# Sheet_Robo_Hand_main.net
KiCad netlist of a schematic drawn in Altium Designer
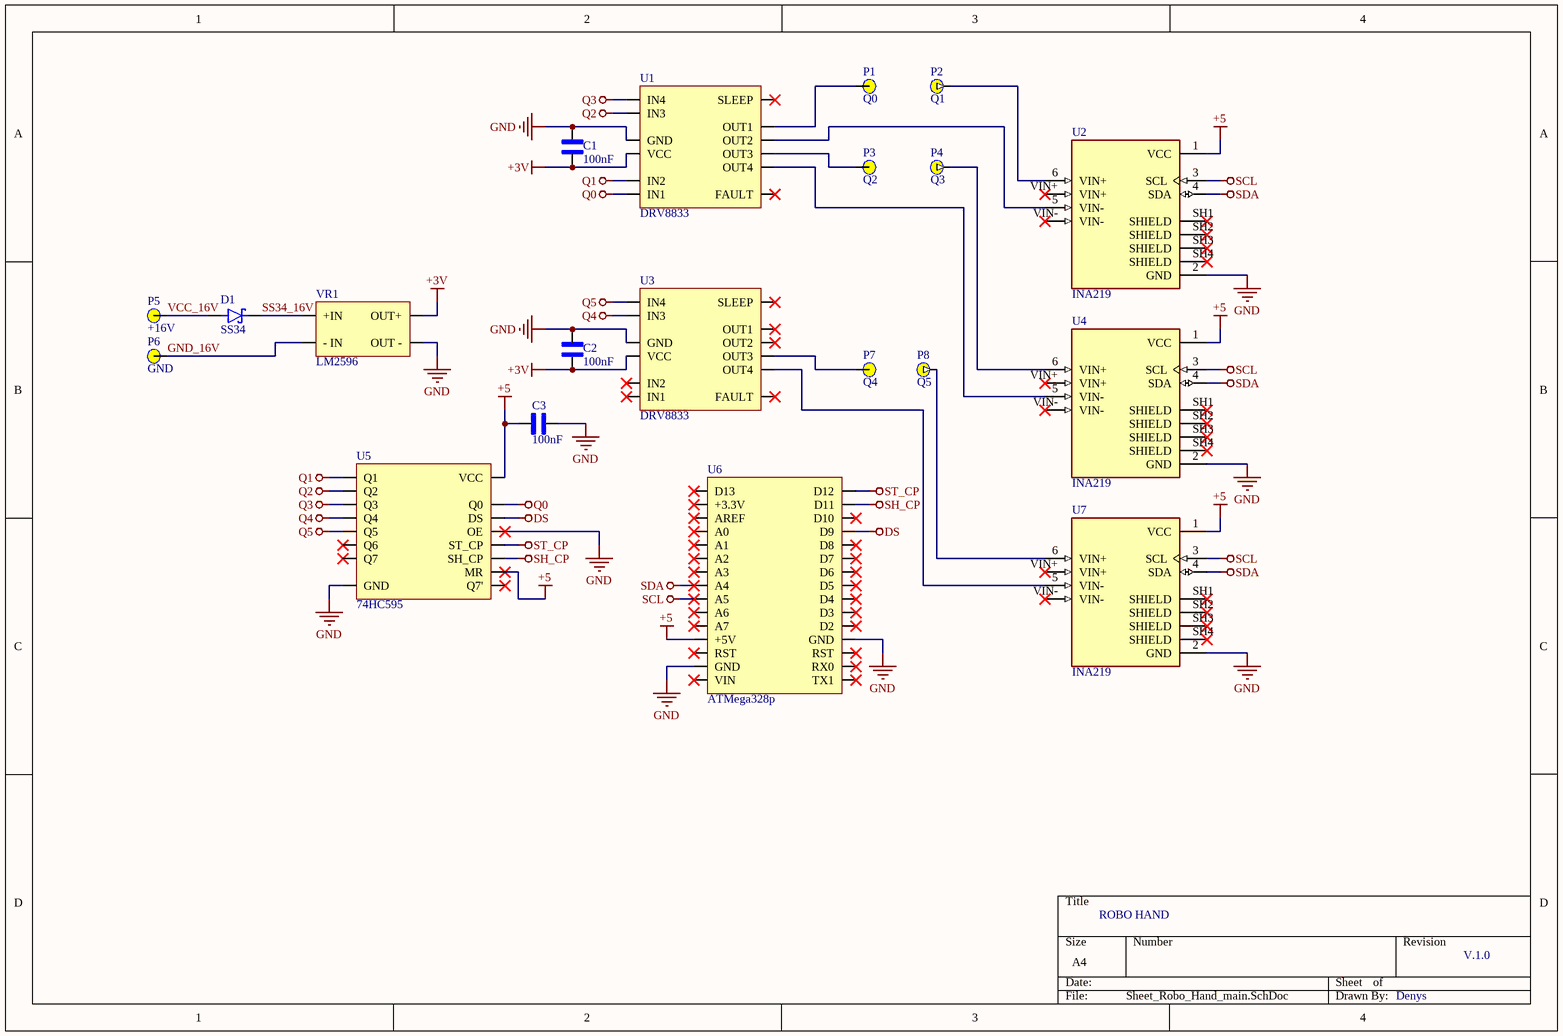
[diagram p0: Sheet_Robo_Hand_main.SchDoc]

(export (version "E")
  (design (tool "Eeschema 10.0.6"))
  (components
    (comp (ref "C1")
      (value "100nF")
      (footprint "CAPC3216X180N")
      (description "Ceramic capacitor SMD 1206 100 nF 50 V 10 % Samsung Electro-Mechanics CL31B104KBCNNNC 4000 pc(s)")
      (fields (field (name "MP") "CL31B104KBCNNNC") (field (name "MF") "Samsung Electro-Mechanics"))
      (libsource (lib "") (part "C_1206_100nF_1"))
    )
    (comp (ref "C2")
      (value "100nF")
      (footprint "CAPC3216X180N")
      (description "Ceramic capacitor SMD 1206 100 nF 50 V 10 % Samsung Electro-Mechanics CL31B104KBCNNNC 4000 pc(s)")
      (fields (field (name "MP") "CL31B104KBCNNNC") (field (name "MF") "Samsung Electro-Mechanics"))
      (libsource (lib "С_1206_100nF") (part "C_1206_100nF"))
    )
    (comp (ref "C3")
      (value "100nF")
      (footprint "CAPC3216X180N")
      (description "Ceramic capacitor SMD 1206 100 nF 50 V 10 % Samsung Electro-Mechanics CL31B104KBCNNNC 4000 pc(s)")
      (fields (field (name "MP") "CL31B104KBCNNNC") (field (name "MF") "Samsung Electro-Mechanics"))
      (libsource (lib "") (part "C_1206_100nF_2"))
    )
    (comp (ref "D1")
      (value "SS34")
      (footprint "DIOM7959X265N")
      (description "SS34 - діод Шоттки")
      (fields (field (name "MF") "onsemi"))
      (libsource (lib "Sch_SS34") (part "Diode_SS34"))
    )
    (comp (ref "P1") (value "Q0") (footprint "PCB_Pin_1") (libsource (lib "Sch_Pin_1") (part "PIN_1")))
    (comp (ref "P2") (value "Q1") (footprint "PCB_Pin_1") (libsource (lib "Sch_Pin_1") (part "PIN_1")))
    (comp (ref "P3") (value "Q2") (footprint "PCB_Pin_1") (libsource (lib "Sch_Pin_1") (part "PIN_1")))
    (comp (ref "P4") (value "Q3") (footprint "PCB_Pin_1") (libsource (lib "Sch_Pin_1") (part "PIN_1")))
    (comp (ref "P5") (value "+16V") (footprint "PCB_Pin_1") (libsource (lib "Sch_Pin_1") (part "PIN_1")))
    (comp (ref "P6") (value "GND") (footprint "PCB_Pin_1") (libsource (lib "Sch_Pin_1") (part "PIN_1")))
    (comp (ref "P7") (value "Q4") (footprint "PCB_Pin_1") (libsource (lib "Sch_Pin_1") (part "PIN_1")))
    (comp (ref "P8") (value "Q5") (footprint "PCB_Pin_1") (libsource (lib "Sch_Pin_1") (part "PIN_1")))
    (comp (ref "U1")
      (value "DRV8833")
      (footprint "PCB_DRV8833")
      (description "Драйвер крокового/колекторних двигунів DRV8833")
      (libsource (lib "Sch_DRV8833") (part "Motor Driver"))
    )
    (comp (ref "U2")
      (value "INA219")
      (footprint "MODULE_INA219")
      (description "INA219 High Side DC Current Sensor Breakout - 26V Â±3.2A Max ¦ Adafruit Industries 904")
      (fields
        (field (name "MF") "Adafruit Industries")
        (field (name "MP") "INA219 High Side DC Current Sensor Breakout - 26V Â±3.2A Max - STEMMA QT")
      )
      (libsource (lib "INA219") (part "INA219"))
    )
    (comp (ref "U3")
      (value "DRV8833")
      (footprint "PCB_DRV8833")
      (description "Драйвер крокового/колекторних двигунів DRV8833")
      (libsource (lib "Sch_DRV8833") (part "Motor Driver"))
    )
    (comp (ref "U4")
      (value "INA219")
      (footprint "MODULE_INA219")
      (description "INA219 High Side DC Current Sensor Breakout - 26V Â±3.2A Max ¦ Adafruit Industries 904")
      (fields
        (field (name "MF") "Adafruit Industries")
        (field (name "MP") "INA219 High Side DC Current Sensor Breakout - 26V Â±3.2A Max - STEMMA QT")
      )
      (libsource (lib "INA219") (part "INA219"))
    )
    (comp (ref "U5")
      (value "74HC595")
      (footprint "PCB_74HC595_Footprint")
      (description "SN74HC595N - вихідний зсувний регістр 74HC595")
      (libsource (lib "Sch_74HC595") (part "SCS-16"))
    )
    (comp (ref "U6")
      (value "ATMega328p")
      (footprint "PCB_ATMega328p")
      (description "DCCduino Nano CH340 - аналог Arduino Nano v3.0 TYPE C")
      (libsource (lib "Sch_ATMega328p") (part "Arduino Nano"))
    )
    (comp (ref "U7")
      (value "INA219")
      (footprint "MODULE_INA219")
      (description "INA219 High Side DC Current Sensor Breakout - 26V Â±3.2A Max ¦ Adafruit Industries 904")
      (fields
        (field (name "MF") "Adafruit Industries")
        (field (name "MP") "INA219 High Side DC Current Sensor Breakout - 26V Â±3.2A Max - STEMMA QT")
      )
      (libsource (lib "INA219") (part "INA219"))
    )
    (comp (ref "VR1")
      (value "LM2596")
      (footprint "DC-DC Step-Down Footprint")
      (description "DC-DC конвертер знижуючий 4.5...40В на 1.5...35В на LM2596")
      (libsource (lib "Sch_LM2596") (part "DC-DC Step-Down"))
    )
  )
  (nets
    (net (code "1") (name "+3V") (class "Default")
      (node (ref "C1") (pin "2") (pinfunction "2_2") (pintype "passive"))
      (node (ref "C2") (pin "1") (pinfunction "1_1") (pintype "passive"))
      (node (ref "U1") (pin "2") (pinfunction "VCC_2") (pintype "power_in"))
      (node (ref "U3") (pin "2") (pinfunction "VCC_2") (pintype "power_in"))
      (node (ref "VR1") (pin "2") (pinfunction "OUT+_2") (pintype "power_in"))
    )
    (net (code "2") (name "+5") (class "Default")
      (node (ref "C3") (pin "2") (pinfunction "2_2") (pintype "passive"))
      (node (ref "U2") (pin "1") (pinfunction "VCC_1") (pintype "power_in"))
      (node (ref "U4") (pin "1") (pinfunction "VCC_1") (pintype "power_in"))
      (node (ref "U5") (pin "14") (pinfunction "MR_14") (pintype "passive"))
      (node (ref "U5") (pin "8") (pinfunction "VCC_8") (pintype "power_in"))
      (node (ref "U6") (pin "3") (pinfunction "+5V_3") (pintype "passive"))
      (node (ref "U7") (pin "1") (pinfunction "VCC_1") (pintype "power_in"))
    )
    (net (code "3") (name "/GND_16V") (class "Default")
      (node (ref "P6") (pin "0") (pinfunction "Pin_0") (pintype "passive"))
      (node (ref "VR1") (pin "0") (pinfunction "-_IN_0") (pintype "power_in"))
    )
    (net (code "4") (name "/SS34_16V") (class "Default")
      (node (ref "D1") (pin "C") (pinfunction "K_C") (pintype "passive"))
      (node (ref "VR1") (pin "1") (pinfunction "+IN_1") (pintype "power_in"))
    )
    (net (code "5") (name "/VCC_16V") (class "Default")
      (node (ref "D1") (pin "A") (pinfunction "A_A") (pintype "passive"))
      (node (ref "P5") (pin "0") (pinfunction "Pin_0") (pintype "passive"))
    )
    (net (code "6") (name "DS") (class "Default")
      (node (ref "U5") (pin "10") (pinfunction "DS_10") (pintype "passive"))
      (node (ref "U6") (pin "18") (pinfunction "D9_18") (pintype "passive"))
    )
    (net (code "7") (name "GND") (class "Default")
      (node (ref "C1") (pin "1") (pinfunction "1_1") (pintype "passive"))
      (node (ref "C2") (pin "2") (pinfunction "2_2") (pintype "passive"))
      (node (ref "C3") (pin "1") (pinfunction "1_1") (pintype "passive"))
      (node (ref "U1") (pin "3") (pinfunction "GND_3") (pintype "power_in"))
      (node (ref "U2") (pin "2") (pinfunction "GND_2") (pintype "power_in"))
      (node (ref "U3") (pin "3") (pinfunction "GND_3") (pintype "power_in"))
      (node (ref "U4") (pin "2") (pinfunction "GND_2") (pintype "power_in"))
      (node (ref "U5") (pin "0") (pinfunction "GND_0") (pintype "power_in"))
      (node (ref "U5") (pin "11") (pinfunction "OE_11") (pintype "passive"))
      (node (ref "U6") (pin "1") (pinfunction "GND_1") (pintype "passive"))
      (node (ref "U6") (pin "26") (pinfunction "GND_26") (pintype "passive"))
      (node (ref "U7") (pin "2") (pinfunction "GND_2") (pintype "power_in"))
      (node (ref "VR1") (pin "3") (pinfunction "OUT_-_3") (pintype "power_in"))
    )
    (net (code "8") (name "Net-(P1-Pin)") (class "Default")
      (node (ref "P1") (pin "0") (pinfunction "Pin_0") (pintype "passive"))
      (node (ref "U1") (pin "7") (pinfunction "OUT1_7") (pintype "bidirectional"))
    )
    (net (code "9") (name "Net-(P2-Pin)") (class "Default")
      (node (ref "P2") (pin "0") (pinfunction "Pin_0") (pintype "passive"))
      (node (ref "U2") (pin "6") (pinfunction "VIN+_6") (pintype "input"))
    )
    (net (code "10") (name "Net-(P3-Pin)") (class "Default")
      (node (ref "P3") (pin "0") (pinfunction "Pin_0") (pintype "passive"))
      (node (ref "U1") (pin "9") (pinfunction "OUT3_9") (pintype "bidirectional"))
    )
    (net (code "11") (name "Net-(P4-Pin)") (class "Default")
      (node (ref "P4") (pin "0") (pinfunction "Pin_0") (pintype "passive"))
      (node (ref "U4") (pin "6") (pinfunction "VIN+_6") (pintype "input"))
    )
    (net (code "12") (name "Net-(P7-Pin)") (class "Default")
      (node (ref "P7") (pin "0") (pinfunction "Pin_0") (pintype "passive"))
      (node (ref "U3") (pin "9") (pinfunction "OUT3_9") (pintype "bidirectional"))
    )
    (net (code "13") (name "Net-(P8-Pin)") (class "Default")
      (node (ref "P8") (pin "0") (pinfunction "Pin_0") (pintype "passive"))
      (node (ref "U7") (pin "6") (pinfunction "VIN+_6") (pintype "input"))
    )
    (net (code "14") (name "Net-(U1-OUT2)") (class "Default")
      (node (ref "U1") (pin "8") (pinfunction "OUT2_8") (pintype "bidirectional"))
      (node (ref "U2") (pin "5") (pinfunction "VIN-_5") (pintype "input"))
    )
    (net (code "15") (name "Net-(U1-OUT4)") (class "Default")
      (node (ref "U1") (pin "10") (pinfunction "OUT4_10") (pintype "bidirectional"))
      (node (ref "U4") (pin "5") (pinfunction "VIN-_5") (pintype "input"))
    )
    (net (code "16") (name "Net-(U3-OUT4)") (class "Default")
      (node (ref "U3") (pin "10") (pinfunction "OUT4_10") (pintype "bidirectional"))
      (node (ref "U7") (pin "5") (pinfunction "VIN-_5") (pintype "input"))
    )
    (net (code "17") (name "Q0") (class "Default")
      (node (ref "U1") (pin "0") (pinfunction "IN1_0") (pintype "passive"))
      (node (ref "U5") (pin "9") (pinfunction "Q0_9") (pintype "passive"))
    )
    (net (code "18") (name "Q1") (class "Default")
      (node (ref "U1") (pin "1") (pinfunction "IN2_1") (pintype "passive"))
      (node (ref "U5") (pin "7") (pinfunction "Q1_7") (pintype "passive"))
    )
    (net (code "19") (name "Q2") (class "Default")
      (node (ref "U1") (pin "4") (pinfunction "IN3_4") (pintype "passive"))
      (node (ref "U5") (pin "6") (pinfunction "Q2_6") (pintype "passive"))
    )
    (net (code "20") (name "Q3") (class "Default")
      (node (ref "U1") (pin "5") (pinfunction "IN4_5") (pintype "passive"))
      (node (ref "U5") (pin "5") (pinfunction "Q3_5") (pintype "passive"))
    )
    (net (code "21") (name "Q4") (class "Default")
      (node (ref "U3") (pin "4") (pinfunction "IN3_4") (pintype "passive"))
      (node (ref "U5") (pin "4") (pinfunction "Q4_4") (pintype "passive"))
    )
    (net (code "22") (name "Q5") (class "Default")
      (node (ref "U3") (pin "5") (pinfunction "IN4_5") (pintype "passive"))
      (node (ref "U5") (pin "3") (pinfunction "Q5_3") (pintype "passive"))
    )
    (net (code "23") (name "SCL") (class "Default")
      (node (ref "U2") (pin "3") (pinfunction "SCL_3") (pintype "input"))
      (node (ref "U4") (pin "3") (pinfunction "SCL_3") (pintype "input"))
      (node (ref "U6") (pin "6") (pinfunction "A5_6") (pintype "passive"))
      (node (ref "U7") (pin "3") (pinfunction "SCL_3") (pintype "input"))
    )
    (net (code "24") (name "SDA") (class "Default")
      (node (ref "U2") (pin "4") (pinfunction "SDA_4") (pintype "bidirectional"))
      (node (ref "U4") (pin "4") (pinfunction "SDA_4") (pintype "bidirectional"))
      (node (ref "U6") (pin "7") (pinfunction "A4_7") (pintype "passive"))
      (node (ref "U7") (pin "4") (pinfunction "SDA_4") (pintype "bidirectional"))
    )
    (net (code "25") (name "SH_CP") (class "Default")
      (node (ref "U5") (pin "13") (pinfunction "SH_CP_13") (pintype "passive"))
      (node (ref "U6") (pin "16") (pinfunction "D11_16") (pintype "passive"))
    )
    (net (code "26") (name "ST_CP") (class "Default")
      (node (ref "U5") (pin "12") (pinfunction "ST_CP_12") (pintype "passive"))
      (node (ref "U6") (pin "15") (pinfunction "D12_15") (pintype "passive"))
    )
    (net (code "27") (name "unconnected-(U1-FAULT-Pad11)") (class "Default")
      (node (ref "U1") (pin "11") (pinfunction "FAULT_11") (pintype "passive+no_connect"))
    )
    (net (code "28") (name "unconnected-(U1-SLEEP-Pad6)") (class "Default")
      (node (ref "U1") (pin "6") (pinfunction "SLEEP_6") (pintype "passive+no_connect"))
    )
    (net (code "29") (name "unconnected-(U2-PadVIN+)") (class "Default")
      (node (ref "U2") (pin "VIN+") (pinfunction "VIN+_VIN+") (pintype "input+no_connect"))
    )
    (net (code "30") (name "unconnected-(U2-PadVIN-)") (class "Default")
      (node (ref "U2") (pin "VIN-") (pinfunction "VIN-_VIN-") (pintype "input+no_connect"))
    )
    (net (code "31") (name "unconnected-(U2-SHIELD-PadSH1)") (class "Default")
      (node (ref "U2") (pin "SH1") (pinfunction "SHIELD_SH1") (pintype "passive+no_connect"))
    )
    (net (code "32") (name "unconnected-(U2-SHIELD-PadSH2)") (class "Default")
      (node (ref "U2") (pin "SH2") (pinfunction "SHIELD_SH2") (pintype "passive+no_connect"))
    )
    (net (code "33") (name "unconnected-(U2-SHIELD-PadSH3)") (class "Default")
      (node (ref "U2") (pin "SH3") (pinfunction "SHIELD_SH3") (pintype "passive+no_connect"))
    )
    (net (code "34") (name "unconnected-(U2-SHIELD-PadSH4)") (class "Default")
      (node (ref "U2") (pin "SH4") (pinfunction "SHIELD_SH4") (pintype "passive+no_connect"))
    )
    (net (code "35") (name "unconnected-(U3-FAULT-Pad11)") (class "Default")
      (node (ref "U3") (pin "11") (pinfunction "FAULT_11") (pintype "passive+no_connect"))
    )
    (net (code "36") (name "unconnected-(U3-IN1-Pad0)") (class "Default")
      (node (ref "U3") (pin "0") (pinfunction "IN1_0") (pintype "passive+no_connect"))
    )
    (net (code "37") (name "unconnected-(U3-IN2-Pad1)") (class "Default")
      (node (ref "U3") (pin "1") (pinfunction "IN2_1") (pintype "passive+no_connect"))
    )
    (net (code "38") (name "unconnected-(U3-OUT1-Pad7)") (class "Default")
      (node (ref "U3") (pin "7") (pinfunction "OUT1_7") (pintype "bidirectional+no_connect"))
    )
    (net (code "39") (name "unconnected-(U3-OUT2-Pad8)") (class "Default")
      (node (ref "U3") (pin "8") (pinfunction "OUT2_8") (pintype "bidirectional+no_connect"))
    )
    (net (code "40") (name "unconnected-(U3-SLEEP-Pad6)") (class "Default")
      (node (ref "U3") (pin "6") (pinfunction "SLEEP_6") (pintype "passive+no_connect"))
    )
    (net (code "41") (name "unconnected-(U4-PadVIN+)") (class "Default")
      (node (ref "U4") (pin "VIN+") (pinfunction "VIN+_VIN+") (pintype "input+no_connect"))
    )
    (net (code "42") (name "unconnected-(U4-PadVIN-)") (class "Default")
      (node (ref "U4") (pin "VIN-") (pinfunction "VIN-_VIN-") (pintype "input+no_connect"))
    )
    (net (code "43") (name "unconnected-(U4-SHIELD-PadSH1)") (class "Default")
      (node (ref "U4") (pin "SH1") (pinfunction "SHIELD_SH1") (pintype "passive+no_connect"))
    )
    (net (code "44") (name "unconnected-(U4-SHIELD-PadSH2)") (class "Default")
      (node (ref "U4") (pin "SH2") (pinfunction "SHIELD_SH2") (pintype "passive+no_connect"))
    )
    (net (code "45") (name "unconnected-(U4-SHIELD-PadSH3)") (class "Default")
      (node (ref "U4") (pin "SH3") (pinfunction "SHIELD_SH3") (pintype "passive+no_connect"))
    )
    (net (code "46") (name "unconnected-(U4-SHIELD-PadSH4)") (class "Default")
      (node (ref "U4") (pin "SH4") (pinfunction "SHIELD_SH4") (pintype "passive+no_connect"))
    )
    (net (code "47") (name "unconnected-(U5-Q6-Pad2)") (class "Default")
      (node (ref "U5") (pin "2") (pinfunction "Q6_2") (pintype "passive+no_connect"))
    )
    (net (code "48") (name "unconnected-(U5-Q7'-Pad15)") (class "Default")
      (node (ref "U5") (pin "15") (pinfunction "Q7'_15") (pintype "passive+no_connect"))
    )
    (net (code "49") (name "unconnected-(U5-Q7-Pad1)") (class "Default")
      (node (ref "U5") (pin "1") (pinfunction "Q7_1") (pintype "passive+no_connect"))
    )
    (net (code "50") (name "unconnected-(U6-+3.3V-Pad13)") (class "Default")
      (node (ref "U6") (pin "13") (pinfunction "+3.3V_13") (pintype "passive+no_connect"))
    )
    (net (code "51") (name "unconnected-(U6-A0-Pad11)") (class "Default")
      (node (ref "U6") (pin "11") (pinfunction "A0_11") (pintype "passive+no_connect"))
    )
    (net (code "52") (name "unconnected-(U6-A1-Pad10)") (class "Default")
      (node (ref "U6") (pin "10") (pinfunction "A1_10") (pintype "passive+no_connect"))
    )
    (net (code "53") (name "unconnected-(U6-A2-Pad9)") (class "Default")
      (node (ref "U6") (pin "9") (pinfunction "A2_9") (pintype "passive+no_connect"))
    )
    (net (code "54") (name "unconnected-(U6-A3-Pad8)") (class "Default")
      (node (ref "U6") (pin "8") (pinfunction "A3_8") (pintype "passive+no_connect"))
    )
    (net (code "55") (name "unconnected-(U6-A6-Pad5)") (class "Default")
      (node (ref "U6") (pin "5") (pinfunction "A6_5") (pintype "passive+no_connect"))
    )
    (net (code "56") (name "unconnected-(U6-A7-Pad4)") (class "Default")
      (node (ref "U6") (pin "4") (pinfunction "A7_4") (pintype "passive+no_connect"))
    )
    (net (code "57") (name "unconnected-(U6-AREF-Pad12)") (class "Default")
      (node (ref "U6") (pin "12") (pinfunction "AREF_12") (pintype "passive+no_connect"))
    )
    (net (code "58") (name "unconnected-(U6-D2-Pad25)") (class "Default")
      (node (ref "U6") (pin "25") (pinfunction "D2_25") (pintype "passive+no_connect"))
    )
    (net (code "59") (name "unconnected-(U6-D3-Pad24)") (class "Default")
      (node (ref "U6") (pin "24") (pinfunction "D3_24") (pintype "passive+no_connect"))
    )
    (net (code "60") (name "unconnected-(U6-D4-Pad23)") (class "Default")
      (node (ref "U6") (pin "23") (pinfunction "D4_23") (pintype "passive+no_connect"))
    )
    (net (code "61") (name "unconnected-(U6-D5-Pad22)") (class "Default")
      (node (ref "U6") (pin "22") (pinfunction "D5_22") (pintype "passive+no_connect"))
    )
    (net (code "62") (name "unconnected-(U6-D6-Pad21)") (class "Default")
      (node (ref "U6") (pin "21") (pinfunction "D6_21") (pintype "passive+no_connect"))
    )
    (net (code "63") (name "unconnected-(U6-D7-Pad20)") (class "Default")
      (node (ref "U6") (pin "20") (pinfunction "D7_20") (pintype "passive+no_connect"))
    )
    (net (code "64") (name "unconnected-(U6-D8-Pad19)") (class "Default")
      (node (ref "U6") (pin "19") (pinfunction "D8_19") (pintype "passive+no_connect"))
    )
    (net (code "65") (name "unconnected-(U6-D10-Pad17)") (class "Default")
      (node (ref "U6") (pin "17") (pinfunction "D10_17") (pintype "passive+no_connect"))
    )
    (net (code "66") (name "unconnected-(U6-D13-Pad14)") (class "Default")
      (node (ref "U6") (pin "14") (pinfunction "D13_14") (pintype "passive+no_connect"))
    )
    (net (code "67") (name "unconnected-(U6-RST-Pad2)") (class "Default")
      (node (ref "U6") (pin "2") (pinfunction "RST_2") (pintype "passive+no_connect"))
    )
    (net (code "68") (name "unconnected-(U6-RST-Pad27)") (class "Default")
      (node (ref "U6") (pin "27") (pinfunction "RST_27") (pintype "passive+no_connect"))
    )
    (net (code "69") (name "unconnected-(U6-RX0-Pad28)") (class "Default")
      (node (ref "U6") (pin "28") (pinfunction "RX0_28") (pintype "passive+no_connect"))
    )
    (net (code "70") (name "unconnected-(U6-TX1-Pad29)") (class "Default")
      (node (ref "U6") (pin "29") (pinfunction "TX1_29") (pintype "passive+no_connect"))
    )
    (net (code "71") (name "unconnected-(U6-VIN-Pad0)") (class "Default")
      (node (ref "U6") (pin "0") (pinfunction "VIN_0") (pintype "passive+no_connect"))
    )
    (net (code "72") (name "unconnected-(U7-PadVIN+)") (class "Default")
      (node (ref "U7") (pin "VIN+") (pinfunction "VIN+_VIN+") (pintype "input+no_connect"))
    )
    (net (code "73") (name "unconnected-(U7-PadVIN-)") (class "Default")
      (node (ref "U7") (pin "VIN-") (pinfunction "VIN-_VIN-") (pintype "input+no_connect"))
    )
    (net (code "74") (name "unconnected-(U7-SHIELD-PadSH1)") (class "Default")
      (node (ref "U7") (pin "SH1") (pinfunction "SHIELD_SH1") (pintype "passive+no_connect"))
    )
    (net (code "75") (name "unconnected-(U7-SHIELD-PadSH2)") (class "Default")
      (node (ref "U7") (pin "SH2") (pinfunction "SHIELD_SH2") (pintype "passive+no_connect"))
    )
    (net (code "76") (name "unconnected-(U7-SHIELD-PadSH3)") (class "Default")
      (node (ref "U7") (pin "SH3") (pinfunction "SHIELD_SH3") (pintype "passive+no_connect"))
    )
    (net (code "77") (name "unconnected-(U7-SHIELD-PadSH4)") (class "Default")
      (node (ref "U7") (pin "SH4") (pinfunction "SHIELD_SH4") (pintype "passive+no_connect"))
    )
  )
)
